# ESP8266_Breakout.net
KiCad netlist of a schematic drawn in EAGLE
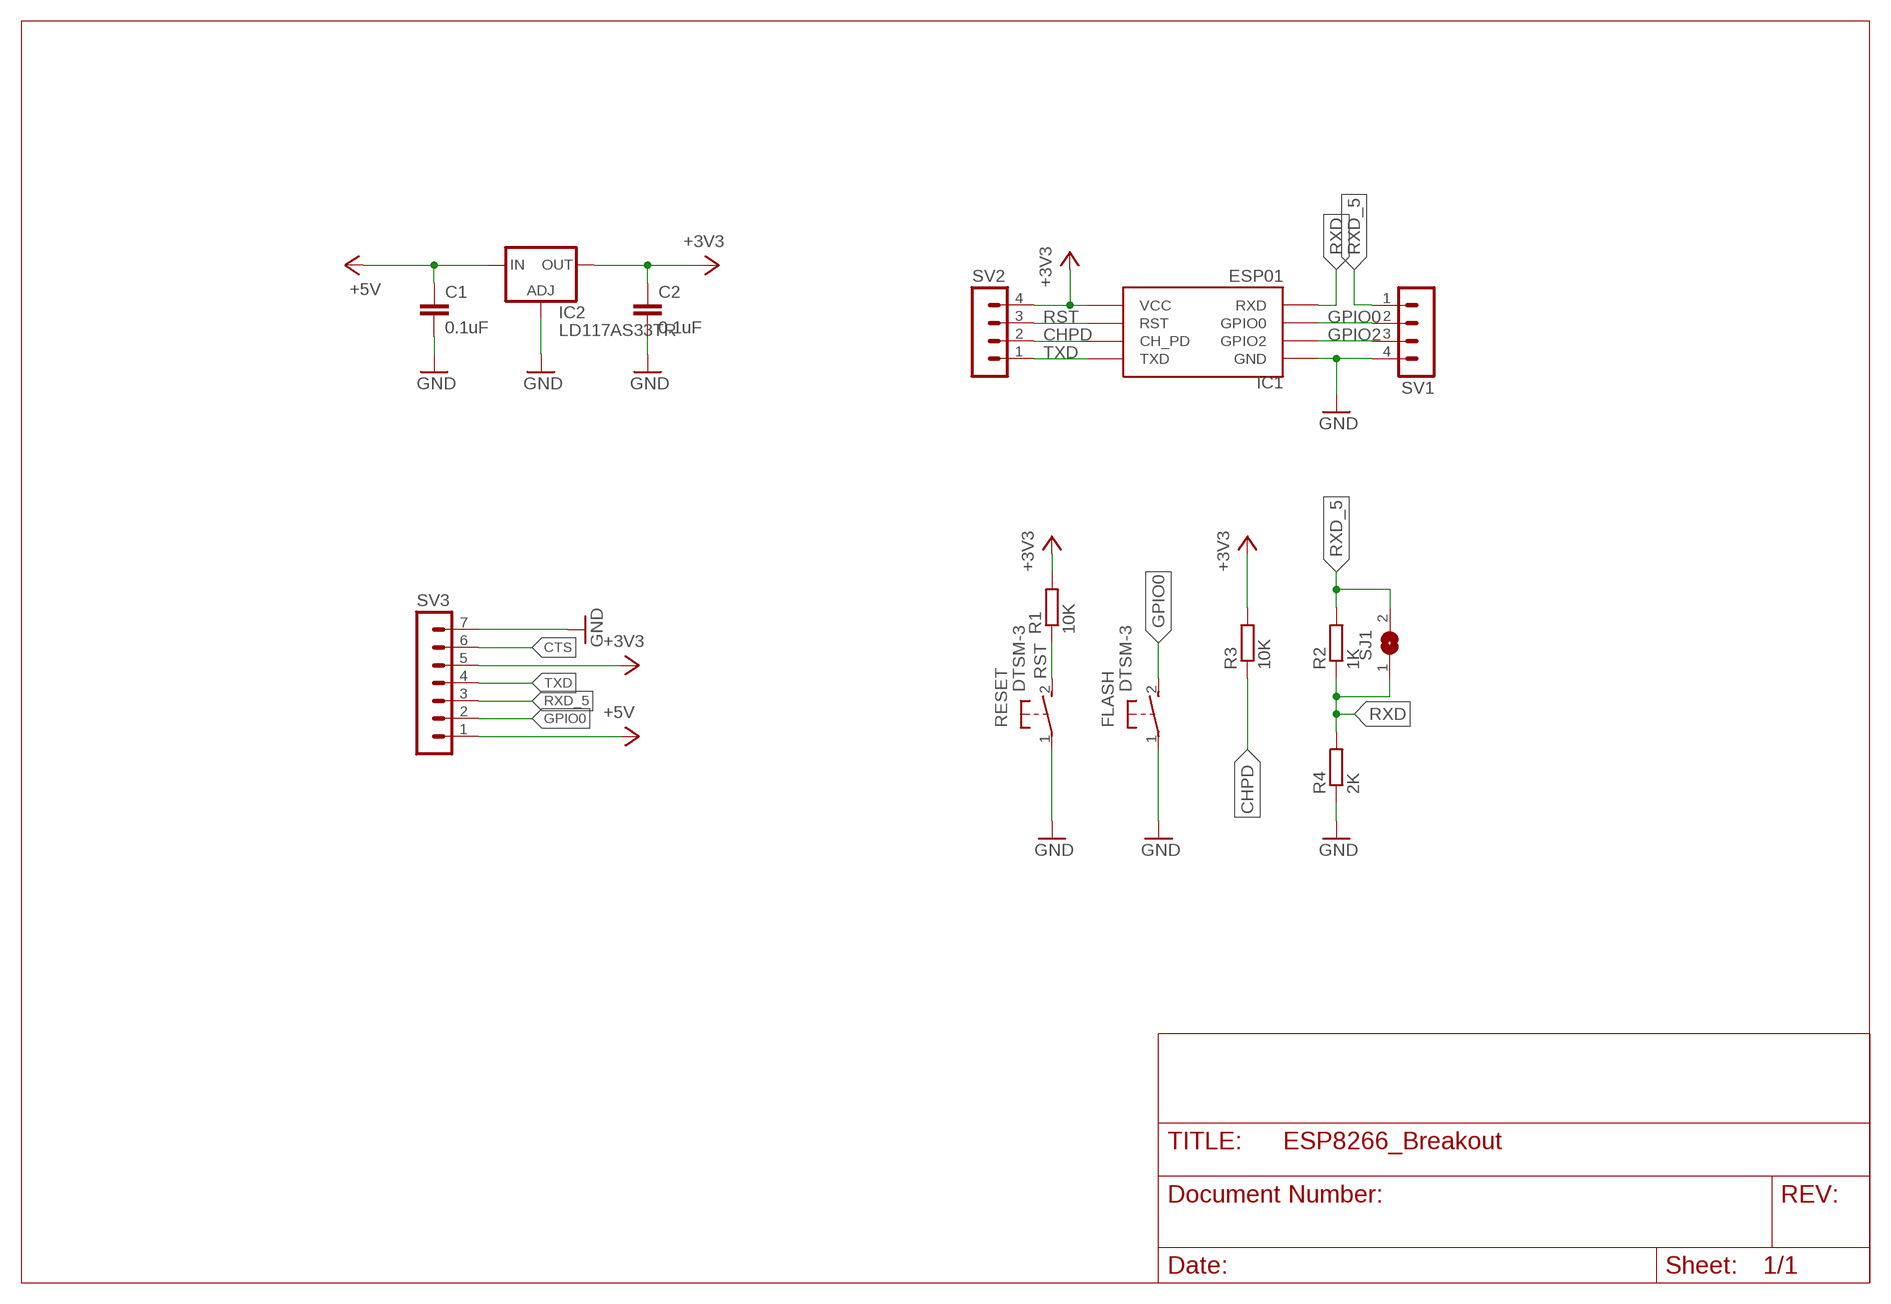
[diagram p0: schematic, sheet 1]

(export (version "E")
  (design (tool "Eeschema 10.0.6"))
  (components
    (comp (ref "C1")
      (value "0.1uF")
      (footprint "eagle-import:C0805K")
      (libsource (lib "eagle-import") (part "C-EUC0805K"))
    )
    (comp (ref "C2")
      (value "0.1uF")
      (footprint "eagle-import:C0805K")
      (libsource (lib "eagle-import") (part "C-EUC0805K"))
    )
    (comp (ref "FLASH")
      (value "DTSM-3")
      (footprint "eagle-import:DTSM-3")
      (libsource (lib "eagle-import") (part "DTSM-3"))
    )
    (comp (ref "IC1")
      (value "ESP01")
      (footprint "eagle-import:ESP01")
      (libsource (lib "eagle-import") (part "ESP01"))
    )
    (comp (ref "IC2")
      (value "LD117AS33TR")
      (footprint "eagle-import:SOT223")
      (libsource (lib "eagle-import") (part "LD117A?S33TR"))
    )
    (comp (ref "R1")
      (value "10K")
      (footprint "eagle-import:M0805")
      (libsource (lib "eagle-import") (part "R-EU_M0805"))
    )
    (comp (ref "R2")
      (value "1K")
      (footprint "eagle-import:R0805")
      (libsource (lib "eagle-import") (part "R-EU_R0805"))
    )
    (comp (ref "R3")
      (value "10K")
      (footprint "eagle-import:R0805")
      (libsource (lib "eagle-import") (part "R-EU_R0805"))
    )
    (comp (ref "R4")
      (value "2K")
      (footprint "eagle-import:R0805")
      (libsource (lib "eagle-import") (part "R-EU_R0805"))
    )
    (comp (ref "RESET")
      (value "DTSM-3")
      (footprint "eagle-import:DTSM-3")
      (libsource (lib "eagle-import") (part "DTSM-3"))
    )
    (comp (ref "SJ1") (value "SJ") (footprint "eagle-import:SJ") (libsource (lib "eagle-import") (part "SJ")))
    (comp (ref "SV1")
      (value "MA04-1")
      (footprint "eagle-import:MA04-1")
      (libsource (lib "eagle-import") (part "MA04-1"))
    )
    (comp (ref "SV2")
      (value "MA04-1")
      (footprint "eagle-import:MA04-1")
      (libsource (lib "eagle-import") (part "MA04-1"))
    )
    (comp (ref "SV3")
      (value "MA07-1")
      (footprint "eagle-import:MA07-1")
      (libsource (lib "eagle-import") (part "MA07-1"))
    )
  )
  (nets
    (net (code "1") (name "+3V3") (class "Default")
      (node (ref "C2") (pin "1") (pinfunction "1_1") (pintype "passive"))
      (node (ref "IC1") (pin "VCC") (pinfunction "VCC_VCC") (pintype "bidirectional"))
      (node (ref "IC2") (pin "4") (pinfunction "OUT_4") (pintype "passive"))
      (node (ref "R1") (pin "2") (pinfunction "2_2") (pintype "passive"))
      (node (ref "R3") (pin "2") (pinfunction "2_2") (pintype "passive"))
      (node (ref "SV2") (pin "4") (pinfunction "4_4") (pintype "passive"))
      (node (ref "SV3") (pin "5") (pinfunction "5_5") (pintype "passive"))
    )
    (net (code "2") (name "+5V") (class "Default")
      (node (ref "C1") (pin "1") (pinfunction "1_1") (pintype "passive"))
      (node (ref "IC2") (pin "3") (pinfunction "IN_3") (pintype "input"))
      (node (ref "SV3") (pin "1") (pinfunction "1_1") (pintype "passive"))
    )
    (net (code "3") (name "/GPIO2") (class "Default")
      (node (ref "IC1") (pin "GPIO2") (pinfunction "GPIO2_GPIO2") (pintype "bidirectional"))
      (node (ref "SV1") (pin "3") (pinfunction "3_3") (pintype "passive"))
    )
    (net (code "4") (name "/RST") (class "Default")
      (node (ref "IC1") (pin "RST") (pinfunction "RST_RST") (pintype "bidirectional"))
      (node (ref "R1") (pin "1") (pinfunction "1_1") (pintype "passive"))
      (node (ref "RESET") (pin "2") (pinfunction "2_2") (pintype "passive"))
      (node (ref "SV2") (pin "3") (pinfunction "3_3") (pintype "passive"))
    )
    (net (code "5") (name "CHPD") (class "Default")
      (node (ref "IC1") (pin "CH_PD") (pinfunction "CH_PD_CH_PD") (pintype "bidirectional"))
      (node (ref "R3") (pin "1") (pinfunction "1_1") (pintype "passive"))
      (node (ref "SV2") (pin "2") (pinfunction "2_2") (pintype "passive"))
    )
    (net (code "6") (name "CTS") (class "Default")
      (node (ref "SV3") (pin "6") (pinfunction "6_6") (pintype "passive"))
    )
    (net (code "7") (name "GND") (class "Default")
      (node (ref "C1") (pin "2") (pinfunction "2_2") (pintype "passive"))
      (node (ref "C2") (pin "2") (pinfunction "2_2") (pintype "passive"))
      (node (ref "FLASH") (pin "1") (pinfunction "1_1") (pintype "passive"))
      (node (ref "IC1") (pin "GND") (pinfunction "GND_GND") (pintype "bidirectional"))
      (node (ref "IC2") (pin "1") (pinfunction "ADJ_1") (pintype "input"))
      (node (ref "R4") (pin "1") (pinfunction "1_1") (pintype "passive"))
      (node (ref "RESET") (pin "1") (pinfunction "1_1") (pintype "passive"))
      (node (ref "SV1") (pin "4") (pinfunction "4_4") (pintype "passive"))
      (node (ref "SV3") (pin "7") (pinfunction "7_7") (pintype "passive"))
    )
    (net (code "8") (name "GPIO0") (class "Default")
      (node (ref "FLASH") (pin "2") (pinfunction "2_2") (pintype "passive"))
      (node (ref "IC1") (pin "GPIO0") (pinfunction "GPIO0_GPIO0") (pintype "bidirectional"))
      (node (ref "SV1") (pin "2") (pinfunction "2_2") (pintype "passive"))
      (node (ref "SV3") (pin "2") (pinfunction "2_2") (pintype "passive"))
    )
    (net (code "9") (name "RXD") (class "Default")
      (node (ref "IC1") (pin "RX") (pinfunction "RXD_RX") (pintype "bidirectional"))
      (node (ref "R2") (pin "1") (pinfunction "1_1") (pintype "passive"))
      (node (ref "R4") (pin "2") (pinfunction "2_2") (pintype "passive"))
      (node (ref "SJ1") (pin "1") (pinfunction "1_1") (pintype "passive"))
    )
    (net (code "10") (name "RXD_5") (class "Default")
      (node (ref "R2") (pin "2") (pinfunction "2_2") (pintype "passive"))
      (node (ref "SJ1") (pin "2") (pinfunction "2_2") (pintype "passive"))
      (node (ref "SV1") (pin "1") (pinfunction "1_1") (pintype "passive"))
      (node (ref "SV3") (pin "3") (pinfunction "3_3") (pintype "passive"))
    )
    (net (code "11") (name "TXD") (class "Default")
      (node (ref "IC1") (pin "TX") (pinfunction "TXD_TX") (pintype "bidirectional"))
      (node (ref "SV2") (pin "1") (pinfunction "1_1") (pintype "passive"))
      (node (ref "SV3") (pin "4") (pinfunction "4_4") (pintype "passive"))
    )
  )
)
